# Debug_switch.net
KiCad netlist of a schematic drawn in Altium Designer
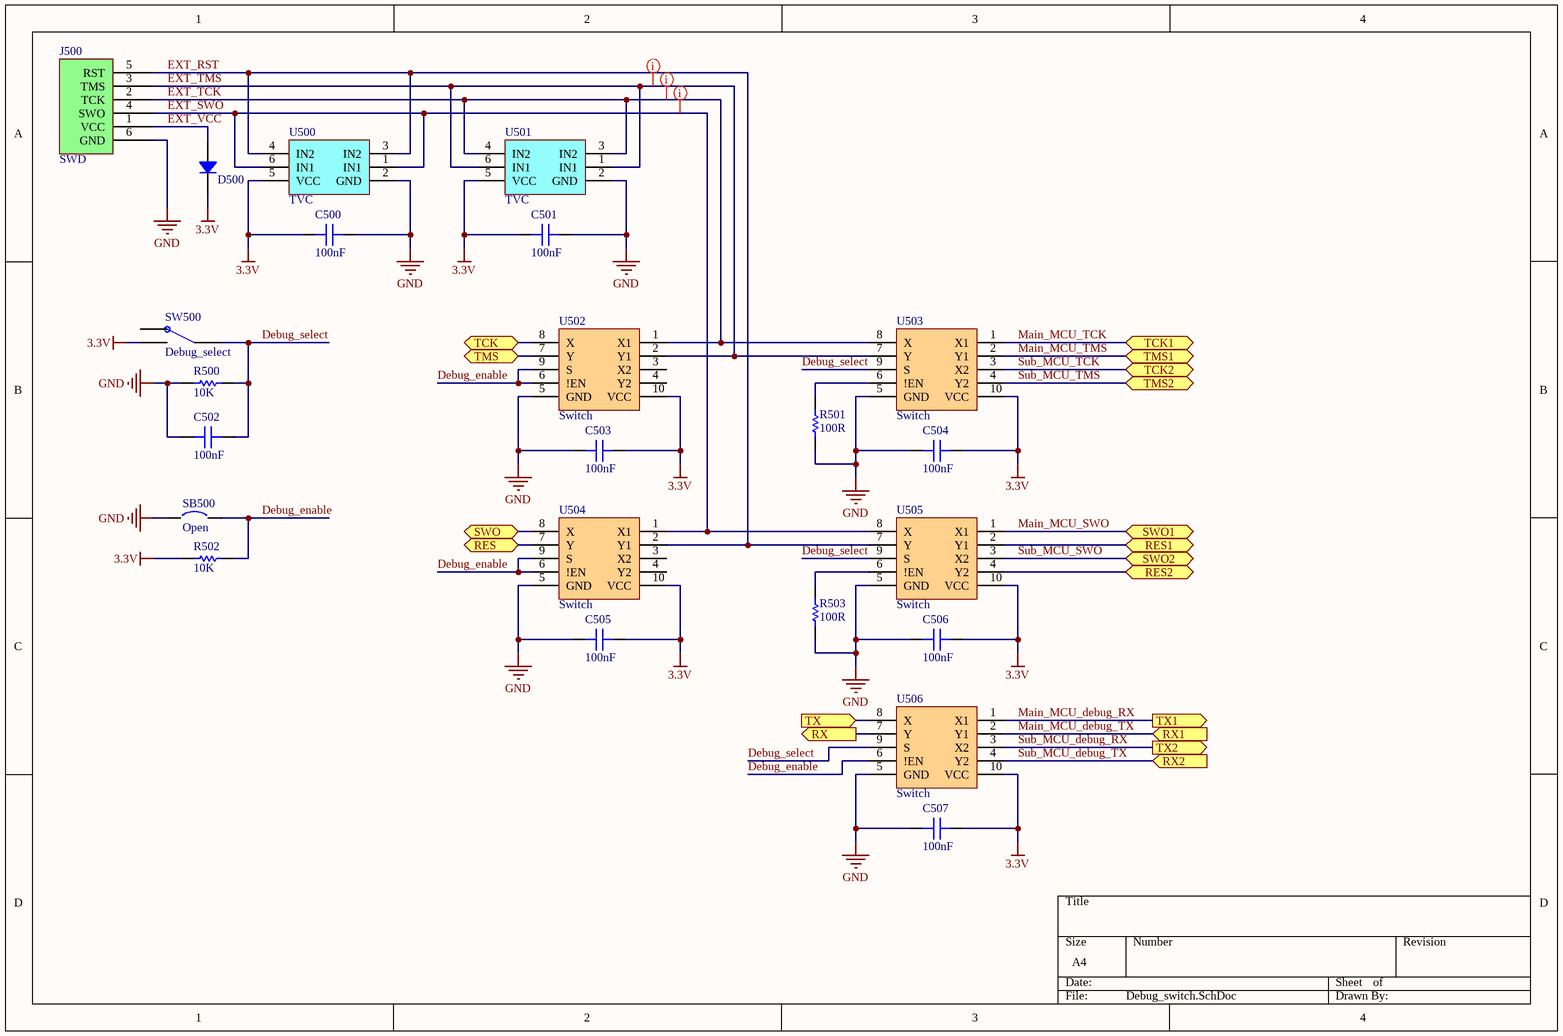
[diagram p0: Debug_switch.SchDoc]

(export (version "E")
  (design (tool "Eeschema 10.0.6"))
  (components
    (comp (ref "C500")
      (value "100nF")
      (footprint "CAP 0603")
      (description "SMT Capacitor")
      (libsource (lib "Schlib1") (part "Capacitor"))
    )
    (comp (ref "C501")
      (value "100nF")
      (footprint "CAP 0603")
      (description "SMT Capacitor")
      (libsource (lib "Schlib1") (part "Capacitor"))
    )
    (comp (ref "C502")
      (value "100nF")
      (footprint "CAP 0603")
      (description "SMT Capacitor")
      (libsource (lib "Schlib1") (part "Capacitor"))
    )
    (comp (ref "C503")
      (value "100nF")
      (footprint "CAP 0603")
      (description "SMT Capacitor")
      (libsource (lib "Schlib1") (part "Capacitor"))
    )
    (comp (ref "C504")
      (value "100nF")
      (footprint "CAP 0603")
      (description "SMT Capacitor")
      (libsource (lib "Schlib1") (part "Capacitor"))
    )
    (comp (ref "C505")
      (value "100nF")
      (footprint "CAP 0603")
      (description "SMT Capacitor")
      (libsource (lib "Schlib1") (part "Capacitor"))
    )
    (comp (ref "C506")
      (value "100nF")
      (footprint "CAP 0603")
      (description "SMT Capacitor")
      (libsource (lib "Schlib1") (part "Capacitor"))
    )
    (comp (ref "C507")
      (value "100nF")
      (footprint "CAP 0603")
      (description "SMT Capacitor")
      (libsource (lib "Schlib1") (part "Capacitor"))
    )
    (comp (ref "D500")
      (value "~")
      (footprint "Bourns DO214AC SMA - duplicate")
      (description "Rectifier Diode")
      (libsource (lib "Schlib1") (part "Diode"))
    )
    (comp (ref "J500")
      (value "SWD")
      (footprint "AMPHENOL_20021121-00006C1LF")
      (libsource (lib "Schlib1") (part "SWD_connector"))
    )
    (comp (ref "R500")
      (value "10K")
      (footprint "RES 0603")
      (description "Resistor")
      (fields (field (name "PUBLISHER") "Altium Limited"))
      (libsource (lib "Schlib1") (part "Res"))
    )
    (comp (ref "R501")
      (value "100R")
      (footprint "RES 0603")
      (description "Resistor")
      (fields (field (name "PUBLISHER") "Altium Limited"))
      (libsource (lib "Schlib1") (part "Res"))
    )
    (comp (ref "R502")
      (value "10K")
      (footprint "RES 0603")
      (description "Resistor")
      (fields (field (name "PUBLISHER") "Altium Limited"))
      (libsource (lib "Schlib1") (part "Res"))
    )
    (comp (ref "R503")
      (value "100R")
      (footprint "RES 0603")
      (description "Resistor")
      (fields (field (name "PUBLISHER") "Altium Limited"))
      (libsource (lib "Schlib1") (part "Res"))
    )
    (comp (ref "SB500")
      (value "Open")
      (footprint "SB_0603")
      (description "Circuit Breaker")
      (fields (field (name "PUBLISHER") "Altium Limited"))
      (libsource (lib "Schlib1") (part "Circuit Breaker"))
    )
    (comp (ref "SW500")
      (value "Debug_select")
      (footprint "SW_JS202011JCQN")
      (libsource (lib "Schlib1") (part "Switch_1"))
    )
    (comp (ref "U500")
      (value "TVC")
      (footprint "SOT95P275X110-6N - duplicate - duplicate")
      (libsource (lib "Schlib1") (part "TVC_protection"))
    )
    (comp (ref "U501")
      (value "TVC")
      (footprint "SOT95P275X110-6N - duplicate - duplicate")
      (libsource (lib "Schlib1") (part "TVC_protection"))
    )
    (comp (ref "U502")
      (value "Switch")
      (footprint "ECEN_1400:PI3USB221AZUAEX")
      (libsource (lib "Schlib1") (part "Switch"))
    )
    (comp (ref "U503")
      (value "Switch")
      (footprint "ECEN_1400:PI3USB221AZUAEX")
      (libsource (lib "Schlib1") (part "Switch"))
    )
    (comp (ref "U504")
      (value "Switch")
      (footprint "ECEN_1400:PI3USB221AZUAEX")
      (libsource (lib "Schlib1") (part "Switch"))
    )
    (comp (ref "U505")
      (value "Switch")
      (footprint "ECEN_1400:PI3USB221AZUAEX")
      (libsource (lib "Schlib1") (part "Switch"))
    )
    (comp (ref "U506")
      (value "Switch")
      (footprint "ECEN_1400:PI3USB221AZUAEX")
      (libsource (lib "Schlib1") (part "Switch"))
    )
  )
  (nets
    (net (code "1") (name "/Debug_enable") (class "Default")
      (node (ref "R502") (pin "2") (pinfunction "2_2") (pintype "passive"))
      (node (ref "SB500") (pin "2") (pinfunction "2_2") (pintype "passive"))
      (node (ref "U502") (pin "6") (pinfunction "!EN_6") (pintype "passive"))
      (node (ref "U502") (pin "9") (pinfunction "S_9") (pintype "passive"))
      (node (ref "U504") (pin "6") (pinfunction "!EN_6") (pintype "passive"))
      (node (ref "U504") (pin "9") (pinfunction "S_9") (pintype "passive"))
      (node (ref "U506") (pin "6") (pinfunction "!EN_6") (pintype "passive"))
    )
    (net (code "2") (name "/Debug_select") (class "Default")
      (node (ref "C502") (pin "2") (pinfunction "2_2") (pintype "passive"))
      (node (ref "R500") (pin "2") (pinfunction "2_2") (pintype "passive"))
      (node (ref "SW500") (pin "2") (pinfunction "2_2") (pintype "passive"))
      (node (ref "U503") (pin "9") (pinfunction "S_9") (pintype "passive"))
      (node (ref "U505") (pin "9") (pinfunction "S_9") (pintype "passive"))
      (node (ref "U506") (pin "9") (pinfunction "S_9") (pintype "passive"))
    )
    (net (code "3") (name "/EXT_RST") (class "Default")
      (node (ref "J500") (pin "5") (pinfunction "RST_5") (pintype "passive"))
      (node (ref "U500") (pin "3") (pinfunction "IN2_3") (pintype "passive"))
      (node (ref "U500") (pin "4") (pinfunction "IN2_4") (pintype "passive"))
      (node (ref "U504") (pin "2") (pinfunction "Y1_2") (pintype "passive"))
      (node (ref "U505") (pin "7") (pinfunction "Y_7") (pintype "passive"))
    )
    (net (code "4") (name "/EXT_SWO") (class "Default")
      (node (ref "J500") (pin "4") (pinfunction "SWO_4") (pintype "passive"))
      (node (ref "U500") (pin "1") (pinfunction "IN1_1") (pintype "passive"))
      (node (ref "U500") (pin "6") (pinfunction "IN1_6") (pintype "passive"))
      (node (ref "U504") (pin "1") (pinfunction "X1_1") (pintype "passive"))
      (node (ref "U505") (pin "8") (pinfunction "X_8") (pintype "passive"))
    )
    (net (code "5") (name "/EXT_TCK") (class "Default")
      (node (ref "J500") (pin "2") (pinfunction "TCK_2") (pintype "passive"))
      (node (ref "U501") (pin "3") (pinfunction "IN2_3") (pintype "passive"))
      (node (ref "U501") (pin "4") (pinfunction "IN2_4") (pintype "passive"))
      (node (ref "U502") (pin "1") (pinfunction "X1_1") (pintype "passive"))
      (node (ref "U503") (pin "8") (pinfunction "X_8") (pintype "passive"))
    )
    (net (code "6") (name "/EXT_TMS") (class "Default")
      (node (ref "J500") (pin "3") (pinfunction "TMS_3") (pintype "passive"))
      (node (ref "U501") (pin "1") (pinfunction "IN1_1") (pintype "passive"))
      (node (ref "U501") (pin "6") (pinfunction "IN1_6") (pintype "passive"))
      (node (ref "U502") (pin "2") (pinfunction "Y1_2") (pintype "passive"))
      (node (ref "U503") (pin "7") (pinfunction "Y_7") (pintype "passive"))
    )
    (net (code "7") (name "/EXT_VCC") (class "Default")
      (node (ref "D500") (pin "1") (pinfunction "1_1") (pintype "passive"))
      (node (ref "J500") (pin "1") (pinfunction "VCC_1") (pintype "passive"))
    )
    (net (code "8") (name "/Main_MCU_SWO") (class "Default")
      (node (ref "U505") (pin "1") (pinfunction "X1_1") (pintype "passive"))
    )
    (net (code "9") (name "/Main_MCU_TCK") (class "Default")
      (node (ref "U503") (pin "1") (pinfunction "X1_1") (pintype "passive"))
    )
    (net (code "10") (name "/Main_MCU_TMS") (class "Default")
      (node (ref "U503") (pin "2") (pinfunction "Y1_2") (pintype "passive"))
    )
    (net (code "11") (name "/Main_MCU_debug_RX") (class "Default")
      (node (ref "U506") (pin "1") (pinfunction "X1_1") (pintype "passive"))
    )
    (net (code "12") (name "/Main_MCU_debug_TX") (class "Default")
      (node (ref "U506") (pin "2") (pinfunction "Y1_2") (pintype "passive"))
    )
    (net (code "13") (name "/RES") (class "Default")
      (node (ref "U504") (pin "7") (pinfunction "Y_7") (pintype "passive"))
    )
    (net (code "14") (name "/RES1") (class "Default")
      (node (ref "U505") (pin "2") (pinfunction "Y1_2") (pintype "passive"))
    )
    (net (code "15") (name "/RES2") (class "Default")
      (node (ref "U505") (pin "4") (pinfunction "Y2_4") (pintype "passive"))
    )
    (net (code "16") (name "/RX") (class "Default")
      (node (ref "U506") (pin "7") (pinfunction "Y_7") (pintype "passive"))
    )
    (net (code "17") (name "/SWO") (class "Default")
      (node (ref "U504") (pin "8") (pinfunction "X_8") (pintype "passive"))
    )
    (net (code "18") (name "/Sub_MCU_SWO") (class "Default")
      (node (ref "U505") (pin "3") (pinfunction "X2_3") (pintype "passive"))
    )
    (net (code "19") (name "/Sub_MCU_TCK") (class "Default")
      (node (ref "U503") (pin "3") (pinfunction "X2_3") (pintype "passive"))
    )
    (net (code "20") (name "/Sub_MCU_TMS") (class "Default")
      (node (ref "U503") (pin "4") (pinfunction "Y2_4") (pintype "passive"))
    )
    (net (code "21") (name "/Sub_MCU_debug_RX") (class "Default")
      (node (ref "U506") (pin "3") (pinfunction "X2_3") (pintype "passive"))
    )
    (net (code "22") (name "/Sub_MCU_debug_TX") (class "Default")
      (node (ref "U506") (pin "4") (pinfunction "Y2_4") (pintype "passive"))
    )
    (net (code "23") (name "/TCK") (class "Default")
      (node (ref "U502") (pin "8") (pinfunction "X_8") (pintype "passive"))
    )
    (net (code "24") (name "/TMS") (class "Default")
      (node (ref "U502") (pin "7") (pinfunction "Y_7") (pintype "passive"))
    )
    (net (code "25") (name "/TX") (class "Default")
      (node (ref "U506") (pin "8") (pinfunction "X_8") (pintype "passive"))
    )
    (net (code "26") (name "3.3V") (class "Default")
      (node (ref "C500") (pin "1") (pinfunction "1_1") (pintype "passive"))
      (node (ref "C501") (pin "1") (pinfunction "1_1") (pintype "passive"))
      (node (ref "C503") (pin "2") (pinfunction "2_2") (pintype "passive"))
      (node (ref "C504") (pin "2") (pinfunction "2_2") (pintype "passive"))
      (node (ref "C505") (pin "2") (pinfunction "2_2") (pintype "passive"))
      (node (ref "C506") (pin "2") (pinfunction "2_2") (pintype "passive"))
      (node (ref "C507") (pin "2") (pinfunction "2_2") (pintype "passive"))
      (node (ref "D500") (pin "2") (pinfunction "2_2") (pintype "passive"))
      (node (ref "R502") (pin "1") (pinfunction "1_1") (pintype "passive"))
      (node (ref "SW500") (pin "3") (pinfunction "3_3") (pintype "passive"))
      (node (ref "U500") (pin "5") (pinfunction "VCC_5") (pintype "passive"))
      (node (ref "U501") (pin "5") (pinfunction "VCC_5") (pintype "passive"))
      (node (ref "U502") (pin "10") (pinfunction "VCC_10") (pintype "passive"))
      (node (ref "U503") (pin "10") (pinfunction "VCC_10") (pintype "passive"))
      (node (ref "U504") (pin "10") (pinfunction "VCC_10") (pintype "passive"))
      (node (ref "U505") (pin "10") (pinfunction "VCC_10") (pintype "passive"))
      (node (ref "U506") (pin "10") (pinfunction "VCC_10") (pintype "passive"))
    )
    (net (code "27") (name "GND") (class "Default")
      (node (ref "C500") (pin "2") (pinfunction "2_2") (pintype "passive"))
      (node (ref "C501") (pin "2") (pinfunction "2_2") (pintype "passive"))
      (node (ref "C502") (pin "1") (pinfunction "1_1") (pintype "passive"))
      (node (ref "C503") (pin "1") (pinfunction "1_1") (pintype "passive"))
      (node (ref "C504") (pin "1") (pinfunction "1_1") (pintype "passive"))
      (node (ref "C505") (pin "1") (pinfunction "1_1") (pintype "passive"))
      (node (ref "C506") (pin "1") (pinfunction "1_1") (pintype "passive"))
      (node (ref "C507") (pin "1") (pinfunction "1_1") (pintype "passive"))
      (node (ref "J500") (pin "6") (pinfunction "GND_6") (pintype "passive"))
      (node (ref "R500") (pin "1") (pinfunction "1_1") (pintype "passive"))
      (node (ref "R501") (pin "1") (pinfunction "1_1") (pintype "passive"))
      (node (ref "R503") (pin "1") (pinfunction "1_1") (pintype "passive"))
      (node (ref "SB500") (pin "1") (pinfunction "1_1") (pintype "passive"))
      (node (ref "U500") (pin "2") (pinfunction "GND_2") (pintype "passive"))
      (node (ref "U501") (pin "2") (pinfunction "GND_2") (pintype "passive"))
      (node (ref "U502") (pin "5") (pinfunction "GND_5") (pintype "passive"))
      (node (ref "U503") (pin "5") (pinfunction "GND_5") (pintype "passive"))
      (node (ref "U504") (pin "5") (pinfunction "GND_5") (pintype "passive"))
      (node (ref "U505") (pin "5") (pinfunction "GND_5") (pintype "passive"))
      (node (ref "U506") (pin "5") (pinfunction "GND_5") (pintype "passive"))
    )
    (net (code "28") (name "Net-(U503-!EN)") (class "Default")
      (node (ref "R501") (pin "2") (pinfunction "2_2") (pintype "passive"))
      (node (ref "U503") (pin "6") (pinfunction "!EN_6") (pintype "passive"))
    )
    (net (code "29") (name "Net-(U505-!EN)") (class "Default")
      (node (ref "R503") (pin "2") (pinfunction "2_2") (pintype "passive"))
      (node (ref "U505") (pin "6") (pinfunction "!EN_6") (pintype "passive"))
    )
    (net (code "30") (name "unconnected-(SW500-Pad1)") (class "Default")
      (node (ref "SW500") (pin "1") (pinfunction "1_1") (pintype "passive"))
    )
    (net (code "31") (name "unconnected-(U502-X2-Pad3)") (class "Default")
      (node (ref "U502") (pin "3") (pinfunction "X2_3") (pintype "passive"))
    )
    (net (code "32") (name "unconnected-(U502-Y2-Pad4)") (class "Default")
      (node (ref "U502") (pin "4") (pinfunction "Y2_4") (pintype "passive"))
    )
    (net (code "33") (name "unconnected-(U504-X2-Pad3)") (class "Default")
      (node (ref "U504") (pin "3") (pinfunction "X2_3") (pintype "passive"))
    )
    (net (code "34") (name "unconnected-(U504-Y2-Pad4)") (class "Default")
      (node (ref "U504") (pin "4") (pinfunction "Y2_4") (pintype "passive"))
    )
  )
)
